# Top.net
KiCad netlist of a schematic drawn in Altium Designer
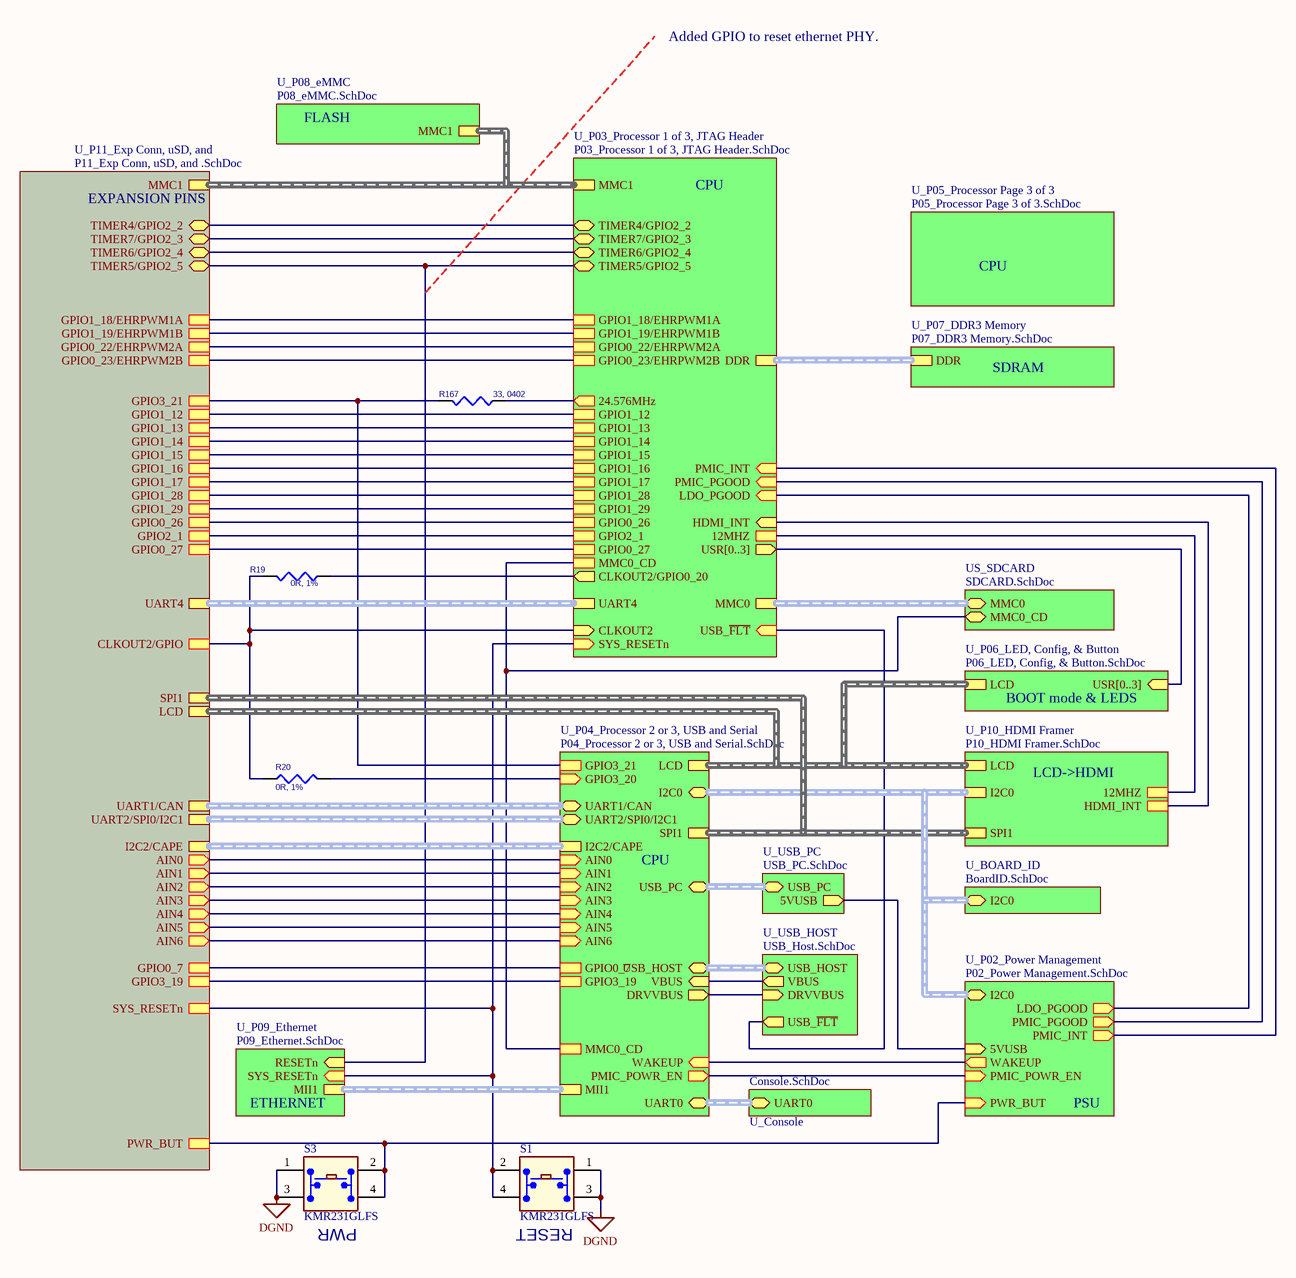
[diagram p0: Top.SchDoc]

(export (version "E")
  (design (tool "Eeschema 10.0.6"))
  (components
    (comp (ref "R19")
      (value "0R, 1%")
      (footprint "402")
      (description "RES 0.0 OHM 1/16W 0402 SMD")
      (fields
        (field (name "MANUFACTURER") "Yageo")
        (field (name "MANUFACTURER PART NUMBER") "RC0402JR-070RL")
      )
      (libsource (lib "BEAGLEBONEBLACK_REV A5B") (part "RES_0_1/16W_1%_0402"))
    )
    (comp (ref "R20")
      (value "0R, 1%")
      (footprint "402")
      (description "RES 0.0 OHM 1/16W 0402 SMD")
      (fields
        (field (name "MANUFACTURER") "Yageo")
        (field (name "MANUFACTURER PART NUMBER") "RC0402JR-070RL")
      )
      (libsource (lib "BEAGLEBONEBLACK_REV A5B") (part "RES_0_1/16W_1%_0402"))
    )
    (comp (ref "R167")
      (value "33, 0402")
      (footprint "402")
      (description "RES 33 OHM 1/16W 5% 0402 SMD")
      (fields
        (field (name "MANUFACTURER") "Panasonic Electronic Components")
        (field (name "MANUFACTURER PART NUMBER") "ERJ-2GEJ330X")
      )
      (libsource (lib "BEAGLEBONEBLACK_REV A5B") (part "RES_33_0402"))
    )
    (comp (ref "S1")
      (value "KMR231GLFS")
      (footprint "SW4SMD_63X161LS")
      (description "Microminiature Tact Switch for SMT")
      (fields (field (name "MANUFACTURER") "C&K Components"))
      (libsource (lib "BEAGLEBONEBLACK_REV A5B") (part "KMR2"))
    )
    (comp (ref "S3")
      (value "KMR231GLFS")
      (footprint "SW4SMD_63X161LS")
      (description "Microminiature Tact Switch for SMT")
      (fields (field (name "MANUFACTURER") "C&K Components"))
      (libsource (lib "") (part "KMR2_1"))
    )
  )
  (nets
    (net (code "3") (name "/24.576MHz") (class "Default")
      (node (ref "R167") (pin "1") (pinfunction "1_1") (pintype "passive"))
    )
    (net (code "11") (name "/CLKOUT2") (class "Default")
      (node (ref "R19") (pin "2") (pinfunction "2_2") (pintype "passive"))
      (node (ref "R20") (pin "1") (pinfunction "1_1") (pintype "passive"))
    )
    (net (code "12") (name "/CLKOUT2{slash}GPIO0_20") (class "Default")
      (node (ref "R19") (pin "1") (pinfunction "1_1") (pintype "passive"))
    )
    (net (code "32") (name "/GPIO3_20") (class "Default")
      (node (ref "R20") (pin "2") (pinfunction "2_2") (pintype "passive"))
    )
    (net (code "33") (name "/GPIO3_21") (class "Default")
      (node (ref "R167") (pin "2") (pinfunction "2_2") (pintype "passive"))
    )
    (net (code "51") (name "/PWR_BUT") (class "Default")
      (node (ref "S3") (pin "2") (pinfunction "A2_2") (pintype "passive"))
      (node (ref "S3") (pin "4") (pinfunction "4_4") (pintype "power_in"))
    )
    (net (code "55") (name "/SYS_RESETn") (class "Default")
      (node (ref "S1") (pin "2") (pinfunction "A2_2") (pintype "passive"))
      (node (ref "S1") (pin "4") (pinfunction "4_4") (pintype "power_in"))
    )
    (net (code "69") (name "DGND") (class "Default")
      (node (ref "S1") (pin "1") (pinfunction "A1_1") (pintype "passive"))
      (node (ref "S1") (pin "3") (pinfunction "A3_3") (pintype "passive"))
      (node (ref "S3") (pin "1") (pinfunction "A1_1") (pintype "passive"))
      (node (ref "S3") (pin "3") (pinfunction "A3_3") (pintype "passive"))
    )
  )
)
